# power_dist.net
KiCad netlist of a schematic drawn in EAGLE
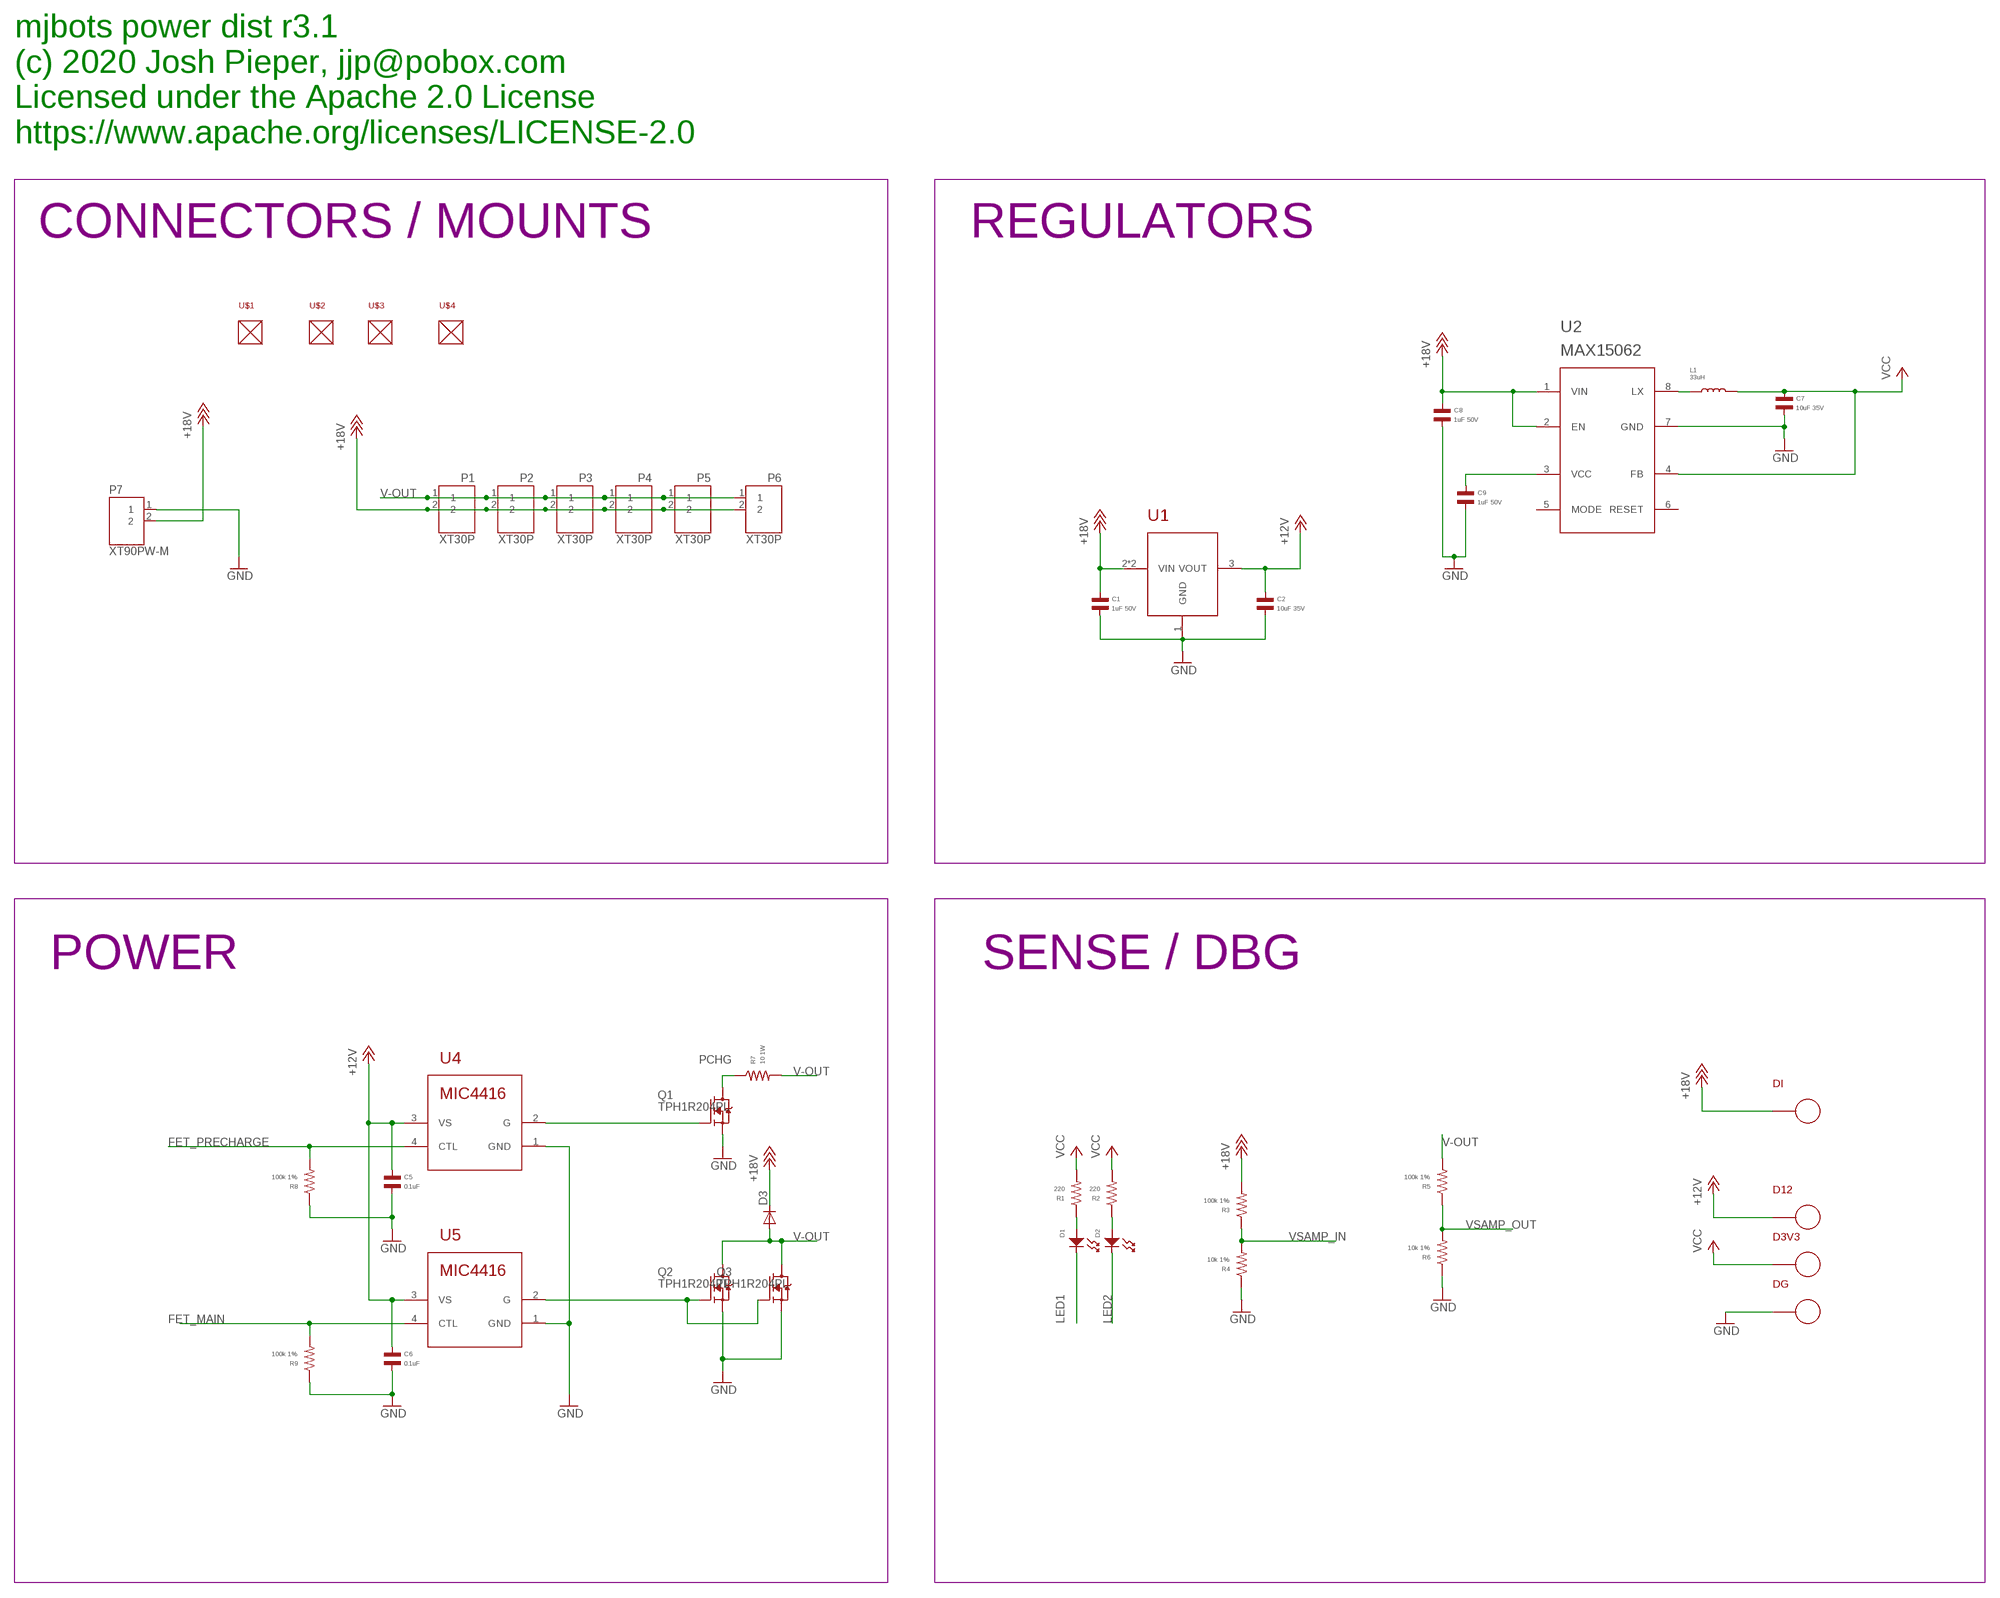
[diagram p0: schematic, sheet 1, part 1 of 2]
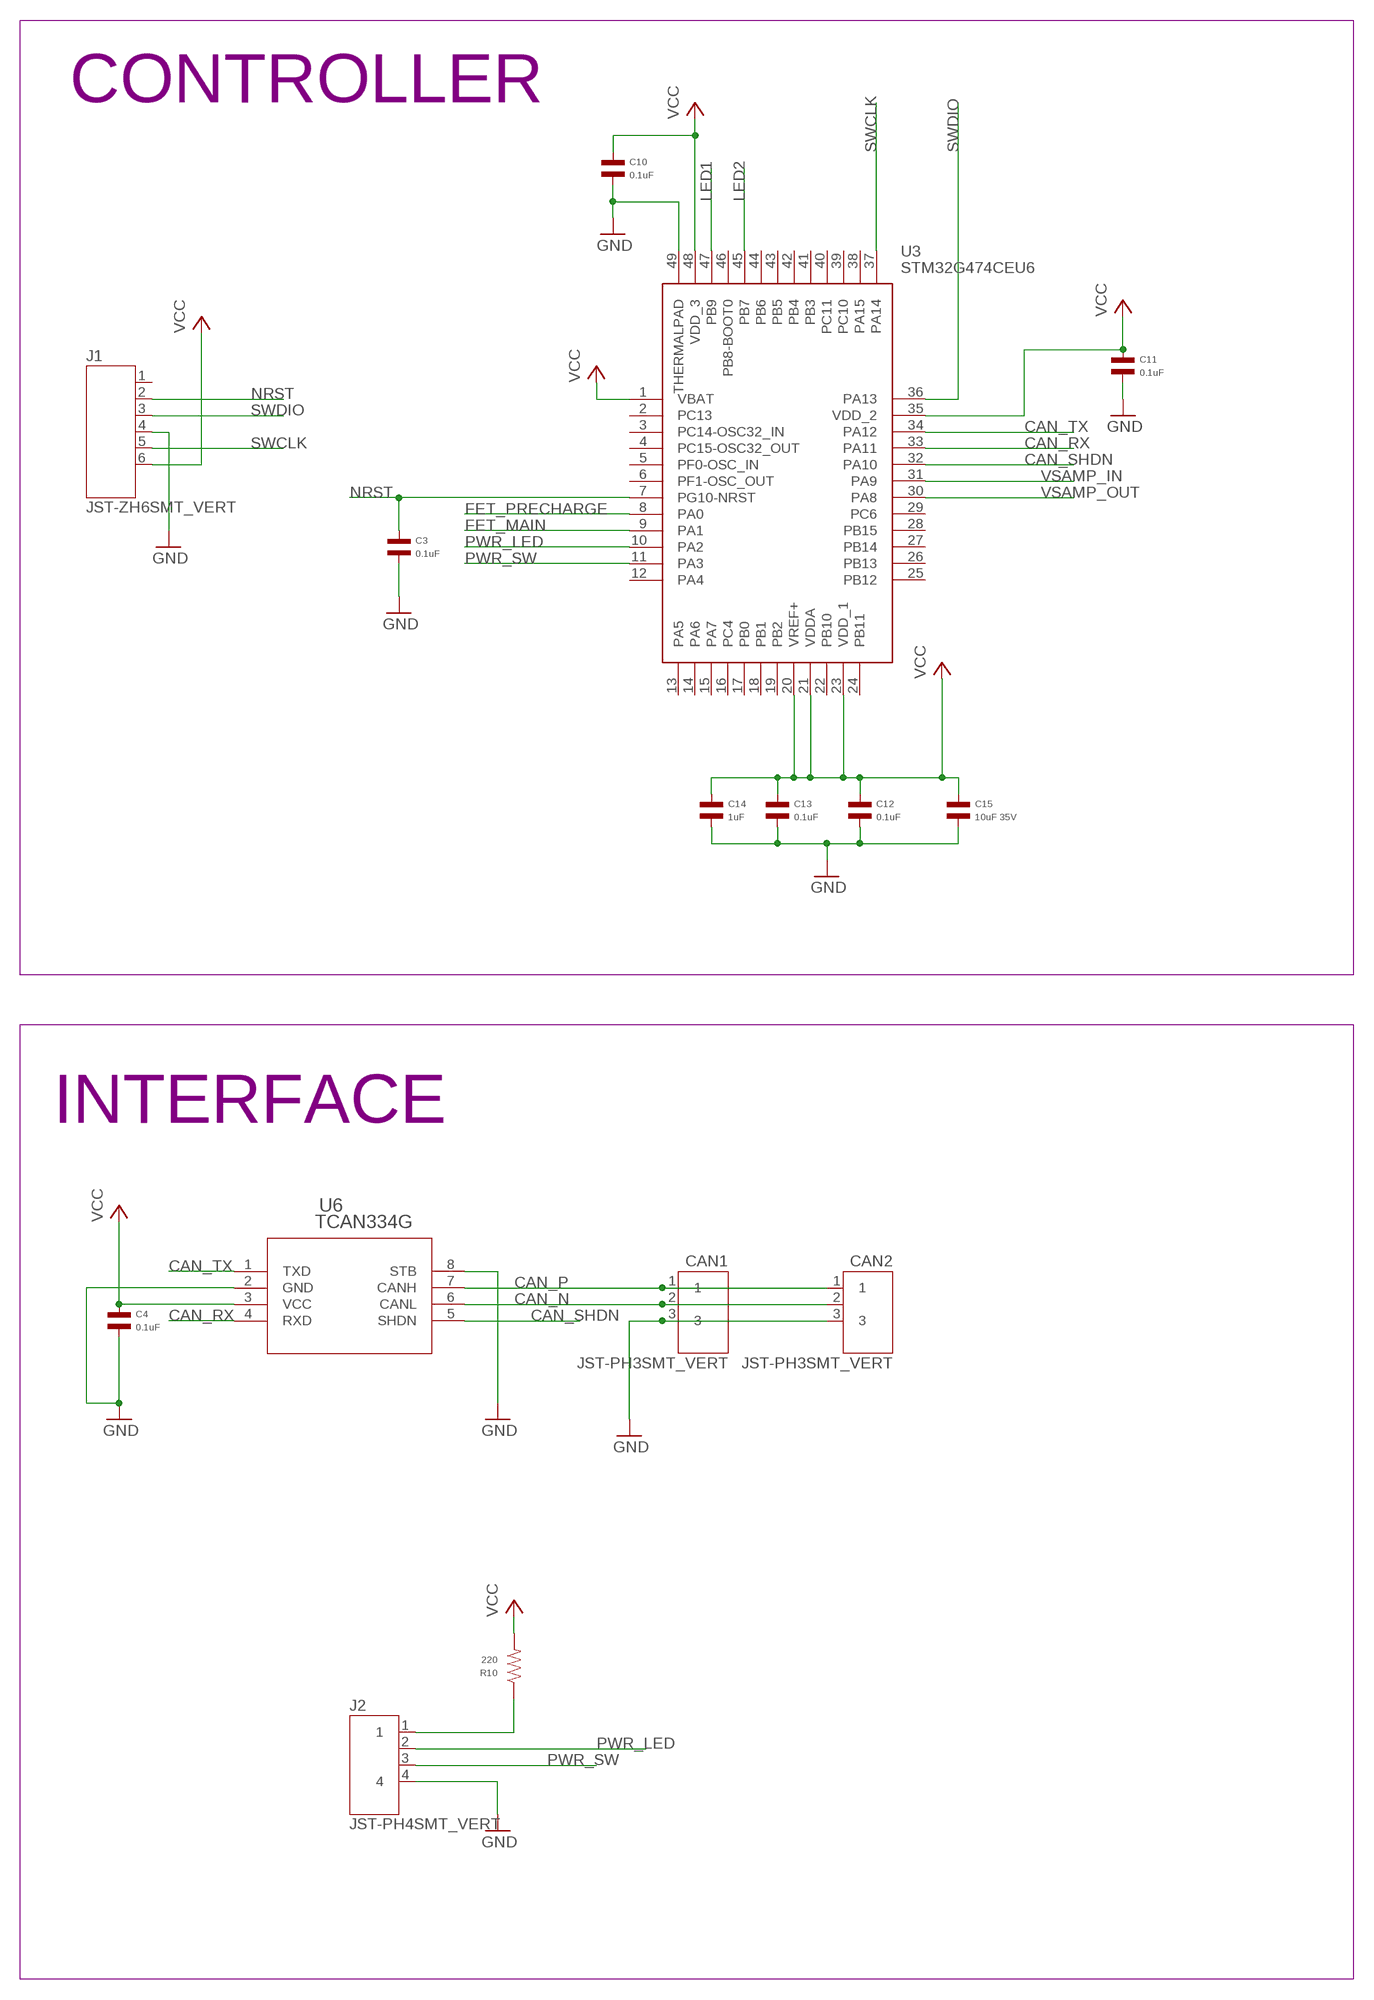
[diagram p1: schematic, sheet 1, part 2 of 2]

(export (version "E")
  (design (tool "Eeschema 10.0.6"))
  (components
    (comp (ref "C1")
      (value "1uF 50V")
      (footprint "eagle-import:C0603")
      (fields (field (name "MF") "SAMSUNG") (field (name "MPN") "CL10A105KB8NNNC"))
      (libsource (lib "eagle-import") (part "CAPACITOR_NP_0603"))
    )
    (comp (ref "C2")
      (value "10uF 35V")
      (footprint "eagle-import:C1206")
      (fields (field (name "MF") "TDK") (field (name "MPN") "CGA5L1X7R1V106K160AC"))
      (libsource (lib "eagle-import") (part "CAPACITOR_NP_1206"))
    )
    (comp (ref "C3")
      (value "0.1uF")
      (footprint "eagle-import:C0402")
      (fields (field (name "HOUSEPART") "1") (field (name "MPN") "MF-CAP-0402-0.1uF"))
      (libsource (lib "eagle-import") (part "CAPACITOR_NP_0402"))
    )
    (comp (ref "C4")
      (value "0.1uF")
      (footprint "eagle-import:C0402")
      (fields (field (name "HOUSEPART") "1") (field (name "MPN") "MF-CAP-0402-0.1uF"))
      (libsource (lib "eagle-import") (part "CAPACITOR_NP_0402"))
    )
    (comp (ref "C5")
      (value "0.1uF")
      (footprint "eagle-import:C0402")
      (fields (field (name "HOUSEPART") "1") (field (name "MPN") "MF-CAP-0402-0.1uF"))
      (libsource (lib "eagle-import") (part "CAPACITOR_NP_0402"))
    )
    (comp (ref "C6")
      (value "0.1uF")
      (footprint "eagle-import:C0402")
      (fields (field (name "HOUSEPART") "1") (field (name "MPN") "MF-CAP-0402-0.1uF"))
      (libsource (lib "eagle-import") (part "CAPACITOR_NP_0402"))
    )
    (comp (ref "C7")
      (value "10uF 35V")
      (footprint "eagle-import:C1206")
      (fields (field (name "MF") "TDK") (field (name "MPN") "CGA5L1X7R1V106K160AC"))
      (libsource (lib "eagle-import") (part "CAPACITOR_NP_1206"))
    )
    (comp (ref "C8")
      (value "1uF 50V")
      (footprint "eagle-import:C0603")
      (fields (field (name "MF") "SAMSUNG") (field (name "MPN") "CL10A105KB8NNNC"))
      (libsource (lib "eagle-import") (part "CAPACITOR_NP_0603"))
    )
    (comp (ref "C9")
      (value "1uF 50V")
      (footprint "eagle-import:C0603")
      (fields (field (name "MF") "SAMSUNG") (field (name "MPN") "CL10A105KB8NNNC"))
      (libsource (lib "eagle-import") (part "CAPACITOR_NP_0603"))
    )
    (comp (ref "C10")
      (value "0.1uF")
      (footprint "eagle-import:C0402")
      (fields (field (name "HOUSEPART") "1") (field (name "MPN") "MF-CAP-0402-0.1uF"))
      (libsource (lib "eagle-import") (part "CAPACITOR_NP_0402"))
    )
    (comp (ref "C11")
      (value "0.1uF")
      (footprint "eagle-import:C0402")
      (fields (field (name "HOUSEPART") "1") (field (name "MPN") "MF-CAP-0402-0.1uF"))
      (libsource (lib "eagle-import") (part "CAPACITOR_NP_0402"))
    )
    (comp (ref "C12")
      (value "0.1uF")
      (footprint "eagle-import:C0402")
      (fields (field (name "HOUSEPART") "1") (field (name "MPN") "MF-CAP-0402-0.1uF"))
      (libsource (lib "eagle-import") (part "CAPACITOR_NP_0402"))
    )
    (comp (ref "C13")
      (value "0.1uF")
      (footprint "eagle-import:C0402")
      (fields (field (name "HOUSEPART") "1") (field (name "MPN") "MF-CAP-0402-0.1uF"))
      (libsource (lib "eagle-import") (part "CAPACITOR_NP_0402"))
    )
    (comp (ref "C14")
      (value "1uF")
      (footprint "eagle-import:C0402")
      (fields (field (name "HOUSEPART") "1") (field (name "MPN") "MF-CAP-0402-1uF"))
      (libsource (lib "eagle-import") (part "CAPACITOR_NP_0402"))
    )
    (comp (ref "C15")
      (value "10uF 35V")
      (footprint "eagle-import:C1206")
      (fields (field (name "MF") "TDK") (field (name "MPN") "CGA5L1X7R1V106K160AC"))
      (libsource (lib "eagle-import") (part "CAPACITOR_NP_1206"))
    )
    (comp (ref "CAN1")
      (value "JST-PH3SMT_VERT")
      (footprint "eagle-import:JST_B3B_PH-SM4-TB(LF)(SN)")
      (fields (field (name "MF") "JST") (field (name "MPN") "B3B-PH-SM4-TB(LF)(SN)"))
      (libsource (lib "eagle-import") (part "JST-PH3SMT_VERT"))
    )
    (comp (ref "CAN2")
      (value "JST-PH3SMT_VERT")
      (footprint "eagle-import:JST_B3B_PH-SM4-TB(LF)(SN)")
      (fields (field (name "MF") "JST") (field (name "MPN") "B3B-PH-SM4-TB(LF)(SN)"))
      (libsource (lib "eagle-import") (part "JST-PH3SMT_VERT"))
    )
    (comp (ref "D1")
      (value "LED_SINGLE-0603")
      (footprint "eagle-import:LED0603")
      (fields
        (field (name "HOUSEPART") "NO")
        (field (name "HOUSEPART_1") "1")
        (field (name "MPN") "MF-LED-0603-RED")
      )
      (libsource (lib "eagle-import") (part "LED_SINGLE-0603"))
    )
    (comp (ref "D2")
      (value "LED_SINGLE-0603")
      (footprint "eagle-import:LED0603")
      (fields
        (field (name "HOUSEPART") "NO")
        (field (name "HOUSEPART_1") "1")
        (field (name "MPN") "MF-LED-0603-RED")
      )
      (libsource (lib "eagle-import") (part "LED_SINGLE-0603"))
    )
    (comp (ref "D3")
      (value "DIODE-")
      (footprint "eagle-import:DO-214AB")
      (fields (field (name "MF") "MICRO COMMERCIAL") (field (name "MPN") "SK510L-TP"))
      (libsource (lib "eagle-import") (part "DIODE-"))
    )
    (comp (ref "D3V3")
      (value "PAD24AWG_PAD")
      (footprint "eagle-import:24AWG_PAD")
      (libsource (lib "eagle-import") (part "PAD24AWG_PAD"))
    )
    (comp (ref "D12")
      (value "PAD24AWG_PAD")
      (footprint "eagle-import:24AWG_PAD")
      (libsource (lib "eagle-import") (part "PAD24AWG_PAD"))
    )
    (comp (ref "DG")
      (value "PAD24AWG_PAD")
      (footprint "eagle-import:24AWG_PAD")
      (libsource (lib "eagle-import") (part "PAD24AWG_PAD"))
    )
    (comp (ref "DI")
      (value "PAD24AWG_PAD")
      (footprint "eagle-import:24AWG_PAD")
      (libsource (lib "eagle-import") (part "PAD24AWG_PAD"))
    )
    (comp (ref "J1")
      (value "JST-ZH6SMT_VERT")
      (footprint "eagle-import:JST_B6B-ZR-SM4-TF(LF)(SN)")
      (fields (field (name "MF") "JST") (field (name "MPN") "B6B-ZR-SM4-TF(LF)(SN)"))
      (libsource (lib "eagle-import") (part "JST-ZH6SMT_VERT"))
    )
    (comp (ref "J2")
      (value "JST-PH4SMT_VERT")
      (footprint "eagle-import:JST_B4B_PH-SM4-TB(LF)(SN)")
      (fields (field (name "MF") "JST") (field (name "MPN") "B4B-PH-SM4-TB(LF)(SN)"))
      (libsource (lib "eagle-import") (part "JST-PH4SMT_VERT"))
    )
    (comp (ref "L1")
      (value "33uH")
      (footprint "eagle-import:L1210")
      (fields (field (name "MF") "TDK") (field (name "MPN") "NLFV32T-330K-EF") (field (name "POPULATE") "1"))
      (libsource (lib "eagle-import") (part "INDUCTOR_1210"))
    )
    (comp (ref "P1")
      (value "XT30P")
      (footprint "eagle-import:XT30P")
      (libsource (lib "eagle-import") (part "XT30P"))
    )
    (comp (ref "P2")
      (value "XT30P")
      (footprint "eagle-import:XT30P")
      (libsource (lib "eagle-import") (part "XT30P"))
    )
    (comp (ref "P3")
      (value "XT30P")
      (footprint "eagle-import:XT30P")
      (libsource (lib "eagle-import") (part "XT30P"))
    )
    (comp (ref "P4")
      (value "XT30P")
      (footprint "eagle-import:XT30P")
      (libsource (lib "eagle-import") (part "XT30P"))
    )
    (comp (ref "P5")
      (value "XT30P")
      (footprint "eagle-import:XT30P")
      (libsource (lib "eagle-import") (part "XT30P"))
    )
    (comp (ref "P6")
      (value "XT30P")
      (footprint "eagle-import:XT30P")
      (libsource (lib "eagle-import") (part "XT30P"))
    )
    (comp (ref "P7")
      (value "XT90PW-M")
      (footprint "eagle-import:XT90PW-M")
      (libsource (lib "eagle-import") (part "XT90PW-M"))
    )
    (comp (ref "Q1")
      (value "TPH1R204PL")
      (footprint "eagle-import:SOP_ADVANCE")
      (fields (field (name "MF") "Toshiba") (field (name "MPN") "TPH1R204PL,L1Q"))
      (libsource (lib "eagle-import") (part "TPH1R204PL"))
    )
    (comp (ref "Q2")
      (value "TPH1R204PL")
      (footprint "eagle-import:SOP_ADVANCE")
      (fields (field (name "MF") "Toshiba") (field (name "MPN") "TPH1R204PL,L1Q"))
      (libsource (lib "eagle-import") (part "TPH1R204PL"))
    )
    (comp (ref "Q3")
      (value "TPH1R204PL")
      (footprint "eagle-import:SOP_ADVANCE")
      (fields (field (name "MF") "Toshiba") (field (name "MPN") "TPH1R204PL,L1Q"))
      (libsource (lib "eagle-import") (part "TPH1R204PL"))
    )
    (comp (ref "R1")
      (value "220")
      (footprint "eagle-import:R0603")
      (fields (field (name "HOUSEPART") "1") (field (name "MPN") "MF-RES-0603-220"))
      (libsource (lib "eagle-import") (part "RESISTOR_0603"))
    )
    (comp (ref "R2")
      (value "220")
      (footprint "eagle-import:R0603")
      (fields (field (name "HOUSEPART") "1") (field (name "MPN") "MF-RES-0603-220"))
      (libsource (lib "eagle-import") (part "RESISTOR_0603"))
    )
    (comp (ref "R3")
      (value "100k 1%")
      (footprint "eagle-import:R0603")
      (fields (field (name "MF") "VISHAY") (field (name "MPN") "CRCW0603100KFKEA"))
      (libsource (lib "eagle-import") (part "RESISTOR_0603"))
    )
    (comp (ref "R4")
      (value "10k 1%")
      (footprint "eagle-import:R0603")
      (fields (field (name "MF") "PANASONIC") (field (name "MPN") "ERJ-3EKF1002V"))
      (libsource (lib "eagle-import") (part "RESISTOR_0603"))
    )
    (comp (ref "R5")
      (value "100k 1%")
      (footprint "eagle-import:R0603")
      (fields (field (name "MF") "VISHAY") (field (name "MPN") "CRCW0603100KFKEA"))
      (libsource (lib "eagle-import") (part "RESISTOR_0603"))
    )
    (comp (ref "R6")
      (value "10k 1%")
      (footprint "eagle-import:R0603")
      (fields (field (name "MF") "PANASONIC") (field (name "MPN") "ERJ-3EKF1002V"))
      (libsource (lib "eagle-import") (part "RESISTOR_0603"))
    )
    (comp (ref "R7")
      (value "10 1W")
      (footprint "eagle-import:R1206")
      (fields (field (name "MF") "Susumu") (field (name "MPN") "HRG3216Q-10R0-D-T1"))
      (libsource (lib "eagle-import") (part "RESISTOR_1206"))
    )
    (comp (ref "R8")
      (value "100k 1%")
      (footprint "eagle-import:R0603")
      (fields (field (name "MF") "VISHAY") (field (name "MPN") "CRCW0603100KFKEA"))
      (libsource (lib "eagle-import") (part "RESISTOR_0603"))
    )
    (comp (ref "R9")
      (value "100k 1%")
      (footprint "eagle-import:R0603")
      (fields (field (name "MF") "VISHAY") (field (name "MPN") "CRCW0603100KFKEA"))
      (libsource (lib "eagle-import") (part "RESISTOR_0603"))
    )
    (comp (ref "R10")
      (value "220")
      (footprint "eagle-import:R0603")
      (fields (field (name "HOUSEPART") "1") (field (name "MPN") "MF-RES-0603-220"))
      (libsource (lib "eagle-import") (part "RESISTOR_0603"))
    )
    (comp (ref "U$1")
      (value "MOUNT")
      (footprint "eagle-import:M2.5MOUNT")
      (libsource (lib "eagle-import") (part "MOUNT"))
    )
    (comp (ref "U$2")
      (value "MOUNT")
      (footprint "eagle-import:M2.5MOUNT")
      (libsource (lib "eagle-import") (part "MOUNT"))
    )
    (comp (ref "U$3")
      (value "MOUNT")
      (footprint "eagle-import:M2.5MOUNT")
      (libsource (lib "eagle-import") (part "MOUNT"))
    )
    (comp (ref "U$4")
      (value "MOUNT")
      (footprint "eagle-import:M2.5MOUNT")
      (libsource (lib "eagle-import") (part "MOUNT"))
    )
    (comp (ref "U1")
      (value "ZXTR2012Z")
      (footprint "eagle-import:SOT89")
      (fields (field (name "MF") "DIODES INC") (field (name "MPN") "ZXTR2012Z-13"))
      (libsource (lib "eagle-import") (part "ZXTR2012Z"))
    )
    (comp (ref "U2")
      (value "MAX150628TDFN")
      (footprint "eagle-import:8TDFN")
      (fields (field (name "MF") "MAXIM") (field (name "MPN") "MAX15062AATA+T"))
      (libsource (lib "eagle-import") (part "MAX150628TDFN"))
    )
    (comp (ref "U3")
      (value "STM32G474CEU6")
      (footprint "eagle-import:QFN50P700X700X60-49N")
      (fields (field (name "MOUSER_PART_NUMBER") "511-STM32G474CEU6") (field (name "MF") "ST"))
      (libsource (lib "eagle-import") (part "STM32G474CEU6"))
    )
    (comp (ref "U4")
      (value "MIC4416")
      (footprint "eagle-import:SOT143")
      (fields (field (name "MF") "MICROCHIP") (field (name "MPN") "MIC4416YM4-TR"))
      (libsource (lib "eagle-import") (part "MIC4416"))
    )
    (comp (ref "U5")
      (value "MIC4416")
      (footprint "eagle-import:SOT143")
      (fields (field (name "MF") "MICROCHIP") (field (name "MPN") "MIC4416YM4-TR"))
      (libsource (lib "eagle-import") (part "MIC4416"))
    )
    (comp (ref "U6")
      (value "TCAN334G")
      (footprint "eagle-import:SOIC8")
      (fields (field (name "MF") "Analog") (field (name "MPN") "LTC2875IS8"))
      (libsource (lib "eagle-import") (part "TCAN334G"))
    )
  )
  (nets
    (net (code "1") (name "+12V") (class "Default")
      (node (ref "C2") (pin "P$1") (pinfunction "P$1_P$1") (pintype "passive"))
      (node (ref "C5") (pin "P$1") (pinfunction "P$1_P$1") (pintype "passive"))
      (node (ref "C6") (pin "P$1") (pinfunction "P$1_P$1") (pintype "passive"))
      (node (ref "D12") (pin "P$1") (pinfunction "P$1_P$1") (pintype "bidirectional"))
      (node (ref "U1") (pin "3") (pinfunction "VOUT_3") (pintype "bidirectional"))
      (node (ref "U4") (pin "3") (pinfunction "VS_3") (pintype "bidirectional"))
      (node (ref "U5") (pin "3") (pinfunction "VS_3") (pintype "bidirectional"))
    )
    (net (code "2") (name "+18V") (class "Default")
      (node (ref "C1") (pin "P$1") (pinfunction "P$1_P$1") (pintype "passive"))
      (node (ref "C8") (pin "P$1") (pinfunction "P$1_P$1") (pintype "passive"))
      (node (ref "D3") (pin "C") (pinfunction "C_C") (pintype "passive"))
      (node (ref "DI") (pin "P$1") (pinfunction "P$1_P$1") (pintype "bidirectional"))
      (node (ref "P1") (pin "2") (pinfunction "2_2") (pintype "passive"))
      (node (ref "P2") (pin "2") (pinfunction "2_2") (pintype "passive"))
      (node (ref "P3") (pin "2") (pinfunction "2_2") (pintype "passive"))
      (node (ref "P4") (pin "2") (pinfunction "2_2") (pintype "passive"))
      (node (ref "P5") (pin "2") (pinfunction "2_2") (pintype "passive"))
      (node (ref "P6") (pin "2") (pinfunction "2_2") (pintype "passive"))
      (node (ref "P7") (pin "2") (pinfunction "2_2") (pintype "passive"))
      (node (ref "R3") (pin "P$2") (pinfunction "P$2_P$2") (pintype "passive"))
      (node (ref "U1") (pin "2") (pinfunction "VIN_2") (pintype "bidirectional"))
      (node (ref "U1") (pin "PAD") (pinfunction "VIN_PAD") (pintype "bidirectional"))
      (node (ref "U2") (pin "1") (pinfunction "VIN_1") (pintype "passive"))
      (node (ref "U2") (pin "2") (pinfunction "EN_2") (pintype "passive"))
    )
    (net (code "3") (name "/CAN_N") (class "Default")
      (node (ref "CAN1") (pin "2") (pinfunction "2_2") (pintype "passive"))
      (node (ref "CAN2") (pin "2") (pinfunction "2_2") (pintype "passive"))
      (node (ref "U6") (pin "6") (pinfunction "CANL_6") (pintype "bidirectional"))
    )
    (net (code "4") (name "/CAN_P") (class "Default")
      (node (ref "CAN1") (pin "1") (pinfunction "1_1") (pintype "passive"))
      (node (ref "CAN2") (pin "1") (pinfunction "1_1") (pintype "passive"))
      (node (ref "U6") (pin "7") (pinfunction "CANH_7") (pintype "bidirectional"))
    )
    (net (code "5") (name "/CAN_RX") (class "Default")
      (node (ref "U3") (pin "33") (pinfunction "PA11_33") (pintype "bidirectional"))
      (node (ref "U6") (pin "4") (pinfunction "RXD_4") (pintype "output"))
    )
    (net (code "6") (name "/CAN_SHDN") (class "Default")
      (node (ref "U3") (pin "32") (pinfunction "PA10_32") (pintype "bidirectional"))
      (node (ref "U6") (pin "5") (pinfunction "SHDN_5") (pintype "input"))
    )
    (net (code "7") (name "/CAN_TX") (class "Default")
      (node (ref "U3") (pin "34") (pinfunction "PA12_34") (pintype "bidirectional"))
      (node (ref "U6") (pin "1") (pinfunction "TXD_1") (pintype "input"))
    )
    (net (code "8") (name "/FET_MAIN") (class "Default")
      (node (ref "R9") (pin "P$2") (pinfunction "P$2_P$2") (pintype "passive"))
      (node (ref "U3") (pin "9") (pinfunction "PA1_9") (pintype "bidirectional"))
      (node (ref "U5") (pin "4") (pinfunction "CTL_4") (pintype "bidirectional"))
    )
    (net (code "9") (name "/FET_PRECHARGE") (class "Default")
      (node (ref "R8") (pin "P$2") (pinfunction "P$2_P$2") (pintype "passive"))
      (node (ref "U3") (pin "8") (pinfunction "PA0_8") (pintype "bidirectional"))
      (node (ref "U4") (pin "4") (pinfunction "CTL_4") (pintype "bidirectional"))
    )
    (net (code "10") (name "/LED1") (class "Default")
      (node (ref "D1") (pin "CATHODE") (pinfunction "CATHODE_CATHODE") (pintype "power_in"))
      (node (ref "U3") (pin "47") (pinfunction "PB9_47") (pintype "bidirectional"))
    )
    (net (code "11") (name "/LED2") (class "Default")
      (node (ref "D2") (pin "CATHODE") (pinfunction "CATHODE_CATHODE") (pintype "power_in"))
      (node (ref "U3") (pin "45") (pinfunction "PB7_45") (pintype "bidirectional"))
    )
    (net (code "12") (name "/NRST") (class "Default")
      (node (ref "C3") (pin "P$1") (pinfunction "P$1_P$1") (pintype "passive"))
      (node (ref "J1") (pin "2") (pinfunction "2_2") (pintype "passive"))
      (node (ref "U3") (pin "7") (pinfunction "PG10-NRST_7") (pintype "bidirectional"))
    )
    (net (code "13") (name "/PCHG") (class "Default")
      (node (ref "Q1") (pin "5") (pinfunction "D_5") (pintype "passive"))
      (node (ref "Q1") (pin "6") (pinfunction "D_6") (pintype "passive"))
      (node (ref "Q1") (pin "7") (pinfunction "D_7") (pintype "passive"))
      (node (ref "Q1") (pin "8") (pinfunction "D_8") (pintype "passive"))
      (node (ref "Q1") (pin "PAD") (pinfunction "D_PAD") (pintype "passive"))
      (node (ref "R7") (pin "P$1") (pinfunction "P$1_P$1") (pintype "passive"))
    )
    (net (code "14") (name "/PWR_LED") (class "Default")
      (node (ref "J2") (pin "2") (pinfunction "2_2") (pintype "passive"))
      (node (ref "U3") (pin "10") (pinfunction "PA2_10") (pintype "bidirectional"))
    )
    (net (code "15") (name "/PWR_SW") (class "Default")
      (node (ref "J2") (pin "3") (pinfunction "3_3") (pintype "passive"))
      (node (ref "U3") (pin "11") (pinfunction "PA3_11") (pintype "bidirectional"))
    )
    (net (code "16") (name "/SWCLK") (class "Default")
      (node (ref "J1") (pin "5") (pinfunction "5_5") (pintype "passive"))
      (node (ref "U3") (pin "37") (pinfunction "PA14_37") (pintype "bidirectional"))
    )
    (net (code "17") (name "/SWDIO") (class "Default")
      (node (ref "J1") (pin "3") (pinfunction "3_3") (pintype "passive"))
      (node (ref "U3") (pin "36") (pinfunction "PA13_36") (pintype "bidirectional"))
    )
    (net (code "18") (name "/V-OUT") (class "Default")
      (node (ref "D3") (pin "A") (pinfunction "A_A") (pintype "passive"))
      (node (ref "P1") (pin "1") (pinfunction "1_1") (pintype "passive"))
      (node (ref "P2") (pin "1") (pinfunction "1_1") (pintype "passive"))
      (node (ref "P3") (pin "1") (pinfunction "1_1") (pintype "passive"))
      (node (ref "P4") (pin "1") (pinfunction "1_1") (pintype "passive"))
      (node (ref "P5") (pin "1") (pinfunction "1_1") (pintype "passive"))
      (node (ref "P6") (pin "1") (pinfunction "1_1") (pintype "passive"))
      (node (ref "Q2") (pin "5") (pinfunction "D_5") (pintype "passive"))
      (node (ref "Q2") (pin "6") (pinfunction "D_6") (pintype "passive"))
      (node (ref "Q2") (pin "7") (pinfunction "D_7") (pintype "passive"))
      (node (ref "Q2") (pin "8") (pinfunction "D_8") (pintype "passive"))
      (node (ref "Q2") (pin "PAD") (pinfunction "D_PAD") (pintype "passive"))
      (node (ref "Q3") (pin "5") (pinfunction "D_5") (pintype "passive"))
      (node (ref "Q3") (pin "6") (pinfunction "D_6") (pintype "passive"))
      (node (ref "Q3") (pin "7") (pinfunction "D_7") (pintype "passive"))
      (node (ref "Q3") (pin "8") (pinfunction "D_8") (pintype "passive"))
      (node (ref "Q3") (pin "PAD") (pinfunction "D_PAD") (pintype "passive"))
      (node (ref "R5") (pin "P$2") (pinfunction "P$2_P$2") (pintype "passive"))
      (node (ref "R7") (pin "P$2") (pinfunction "P$2_P$2") (pintype "passive"))
    )
    (net (code "19") (name "/VSAMP_IN") (class "Default")
      (node (ref "R3") (pin "P$1") (pinfunction "P$1_P$1") (pintype "passive"))
      (node (ref "R4") (pin "P$2") (pinfunction "P$2_P$2") (pintype "passive"))
      (node (ref "U3") (pin "31") (pinfunction "PA9_31") (pintype "bidirectional"))
    )
    (net (code "20") (name "/VSAMP_OUT") (class "Default")
      (node (ref "R5") (pin "P$1") (pinfunction "P$1_P$1") (pintype "passive"))
      (node (ref "R6") (pin "P$2") (pinfunction "P$2_P$2") (pintype "passive"))
      (node (ref "U3") (pin "30") (pinfunction "PA8_30") (pintype "bidirectional"))
    )
    (net (code "21") (name "GND") (class "Default")
      (node (ref "C1") (pin "P$2") (pinfunction "P$2_P$2") (pintype "passive"))
      (node (ref "C10") (pin "P$2") (pinfunction "P$2_P$2") (pintype "passive"))
      (node (ref "C11") (pin "P$2") (pinfunction "P$2_P$2") (pintype "passive"))
      (node (ref "C12") (pin "P$2") (pinfunction "P$2_P$2") (pintype "passive"))
      (node (ref "C13") (pin "P$2") (pinfunction "P$2_P$2") (pintype "passive"))
      (node (ref "C14") (pin "P$2") (pinfunction "P$2_P$2") (pintype "passive"))
      (node (ref "C15") (pin "P$2") (pinfunction "P$2_P$2") (pintype "passive"))
      (node (ref "C2") (pin "P$2") (pinfunction "P$2_P$2") (pintype "passive"))
      (node (ref "C3") (pin "P$2") (pinfunction "P$2_P$2") (pintype "passive"))
      (node (ref "C4") (pin "P$2") (pinfunction "P$2_P$2") (pintype "passive"))
      (node (ref "C5") (pin "P$2") (pinfunction "P$2_P$2") (pintype "passive"))
      (node (ref "C6") (pin "P$2") (pinfunction "P$2_P$2") (pintype "passive"))
      (node (ref "C7") (pin "P$2") (pinfunction "P$2_P$2") (pintype "passive"))
      (node (ref "C8") (pin "P$2") (pinfunction "P$2_P$2") (pintype "passive"))
      (node (ref "C9") (pin "P$2") (pinfunction "P$2_P$2") (pintype "passive"))
      (node (ref "CAN1") (pin "3") (pinfunction "3_3") (pintype "passive"))
      (node (ref "CAN2") (pin "3") (pinfunction "3_3") (pintype "passive"))
      (node (ref "DG") (pin "P$1") (pinfunction "P$1_P$1") (pintype "bidirectional"))
      (node (ref "J1") (pin "4") (pinfunction "4_4") (pintype "passive"))
      (node (ref "J2") (pin "4") (pinfunction "4_4") (pintype "passive"))
      (node (ref "P7") (pin "1") (pinfunction "1_1") (pintype "passive"))
      (node (ref "Q1") (pin "1") (pinfunction "S_1") (pintype "passive"))
      (node (ref "Q1") (pin "2") (pinfunction "S_2") (pintype "passive"))
      (node (ref "Q1") (pin "3") (pinfunction "S_3") (pintype "passive"))
      (node (ref "Q2") (pin "1") (pinfunction "S_1") (pintype "passive"))
      (node (ref "Q2") (pin "2") (pinfunction "S_2") (pintype "passive"))
      (node (ref "Q2") (pin "3") (pinfunction "S_3") (pintype "passive"))
      (node (ref "Q3") (pin "1") (pinfunction "S_1") (pintype "passive"))
      (node (ref "Q3") (pin "2") (pinfunction "S_2") (pintype "passive"))
      (node (ref "Q3") (pin "3") (pinfunction "S_3") (pintype "passive"))
      (node (ref "R4") (pin "P$1") (pinfunction "P$1_P$1") (pintype "passive"))
      (node (ref "R6") (pin "P$1") (pinfunction "P$1_P$1") (pintype "passive"))
      (node (ref "R8") (pin "P$1") (pinfunction "P$1_P$1") (pintype "passive"))
      (node (ref "R9") (pin "P$1") (pinfunction "P$1_P$1") (pintype "passive"))
      (node (ref "U1") (pin "1") (pinfunction "GND_1") (pintype "bidirectional"))
      (node (ref "U2") (pin "7") (pinfunction "GND_7") (pintype "passive"))
      (node (ref "U3") (pin "49") (pinfunction "THERMALPAD_49") (pintype "bidirectional"))
      (node (ref "U4") (pin "1") (pinfunction "GND_1") (pintype "bidirectional"))
      (node (ref "U5") (pin "1") (pinfunction "GND_1") (pintype "bidirectional"))
      (node (ref "U6") (pin "2") (pinfunction "GND_2") (pintype "power_in"))
      (node (ref "U6") (pin "8") (pinfunction "STB_8") (pintype "input"))
    )
    (net (code "22") (name "Net-(D1-PadANODE)") (class "Default")
      (node (ref "D1") (pin "ANODE") (pinfunction "ANODE_ANODE") (pintype "power_in"))
      (node (ref "R1") (pin "P$1") (pinfunction "P$1_P$1") (pintype "passive"))
    )
    (net (code "23") (name "Net-(D2-PadANODE)") (class "Default")
      (node (ref "D2") (pin "ANODE") (pinfunction "ANODE_ANODE") (pintype "power_in"))
      (node (ref "R2") (pin "P$1") (pinfunction "P$1_P$1") (pintype "passive"))
    )
    (net (code "24") (name "Net-(J2-Pad1)") (class "Default")
      (node (ref "J2") (pin "1") (pinfunction "1_1") (pintype "passive"))
      (node (ref "R10") (pin "P$1") (pinfunction "P$1_P$1") (pintype "passive"))
    )
    (net (code "25") (name "Net-(Q1-G)") (class "Default")
      (node (ref "Q1") (pin "4") (pinfunction "G_4") (pintype "passive"))
      (node (ref "U4") (pin "2") (pinfunction "G_2") (pintype "bidirectional"))
    )
    (net (code "26") (name "Net-(Q2-G)") (class "Default")
      (node (ref "Q2") (pin "4") (pinfunction "G_4") (pintype "passive"))
      (node (ref "Q3") (pin "4") (pinfunction "G_4") (pintype "passive"))
      (node (ref "U5") (pin "2") (pinfunction "G_2") (pintype "bidirectional"))
    )
    (net (code "27") (name "Net-(U2-LX)") (class "Default")
      (node (ref "L1") (pin "P$1") (pinfunction "P$1_P$1") (pintype "passive"))
      (node (ref "U2") (pin "8") (pinfunction "LX_8") (pintype "passive"))
    )
    (net (code "28") (name "Net-(U2-VCC)") (class "Default")
      (node (ref "C9") (pin "P$1") (pinfunction "P$1_P$1") (pintype "passive"))
      (node (ref "U2") (pin "3") (pinfunction "VCC_3") (pintype "passive"))
    )
    (net (code "29") (name "VCC") (class "Default")
      (node (ref "C10") (pin "P$1") (pinfunction "P$1_P$1") (pintype "passive"))
      (node (ref "C11") (pin "P$1") (pinfunction "P$1_P$1") (pintype "passive"))
      (node (ref "C12") (pin "P$1") (pinfunction "P$1_P$1") (pintype "passive"))
      (node (ref "C13") (pin "P$1") (pinfunction "P$1_P$1") (pintype "passive"))
      (node (ref "C14") (pin "P$1") (pinfunction "P$1_P$1") (pintype "passive"))
      (node (ref "C15") (pin "P$1") (pinfunction "P$1_P$1") (pintype "passive"))
      (node (ref "C4") (pin "P$1") (pinfunction "P$1_P$1") (pintype "passive"))
      (node (ref "C7") (pin "P$1") (pinfunction "P$1_P$1") (pintype "passive"))
      (node (ref "D3V3") (pin "P$1") (pinfunction "P$1_P$1") (pintype "bidirectional"))
      (node (ref "J1") (pin "6") (pinfunction "6_6") (pintype "passive"))
      (node (ref "L1") (pin "P$2") (pinfunction "P$2_P$2") (pintype "passive"))
      (node (ref "R1") (pin "P$2") (pinfunction "P$2_P$2") (pintype "passive"))
      (node (ref "R10") (pin "P$2") (pinfunction "P$2_P$2") (pintype "passive"))
      (node (ref "R2") (pin "P$2") (pinfunction "P$2_P$2") (pintype "passive"))
      (node (ref "U2") (pin "4") (pinfunction "FB_4") (pintype "passive"))
      (node (ref "U3") (pin "1") (pinfunction "VBAT_1") (pintype "bidirectional"))
      (node (ref "U3") (pin "20") (pinfunction "VREF+_20") (pintype "bidirectional"))
      (node (ref "U3") (pin "21") (pinfunction "VDDA_21") (pintype "bidirectional"))
      (node (ref "U3") (pin "23") (pinfunction "VDD_1_23") (pintype "bidirectional"))
      (node (ref "U3") (pin "35") (pinfunction "VDD_2_35") (pintype "bidirectional"))
      (node (ref "U3") (pin "48") (pinfunction "VDD_3_48") (pintype "bidirectional"))
      (node (ref "U6") (pin "3") (pinfunction "VCC_3") (pintype "power_in"))
    )
    (net (code "30") (name "unconnected-(J1-Pad1)") (class "Default")
      (node (ref "J1") (pin "1") (pinfunction "1_1") (pintype "passive"))
    )
    (net (code "31") (name "unconnected-(U2-MODE-Pad5)") (class "Default")
      (node (ref "U2") (pin "5") (pinfunction "MODE_5") (pintype "passive"))
    )
    (net (code "32") (name "unconnected-(U2-RESET-Pad6)") (class "Default")
      (node (ref "U2") (pin "6") (pinfunction "RESET_6") (pintype "passive"))
    )
    (net (code "33") (name "unconnected-(U3-PA4-Pad12)") (class "Default")
      (node (ref "U3") (pin "12") (pinfunction "PA4_12") (pintype "bidirectional"))
    )
    (net (code "34") (name "unconnected-(U3-PA5-Pad13)") (class "Default")
      (node (ref "U3") (pin "13") (pinfunction "PA5_13") (pintype "bidirectional"))
    )
    (net (code "35") (name "unconnected-(U3-PA6-Pad14)") (class "Default")
      (node (ref "U3") (pin "14") (pinfunction "PA6_14") (pintype "bidirectional"))
    )
    (net (code "36") (name "unconnected-(U3-PA7-Pad15)") (class "Default")
      (node (ref "U3") (pin "15") (pinfunction "PA7_15") (pintype "bidirectional"))
    )
    (net (code "37") (name "unconnected-(U3-PA15-Pad38)") (class "Default")
      (node (ref "U3") (pin "38") (pinfunction "PA15_38") (pintype "bidirectional"))
    )
    (net (code "38") (name "unconnected-(U3-PB0-Pad17)") (class "Default")
      (node (ref "U3") (pin "17") (pinfunction "PB0_17") (pintype "bidirectional"))
    )
    (net (code "39") (name "unconnected-(U3-PB1-Pad18)") (class "Default")
      (node (ref "U3") (pin "18") (pinfunction "PB1_18") (pintype "bidirectional"))
    )
    (net (code "40") (name "unconnected-(U3-PB2-Pad19)") (class "Default")
      (node (ref "U3") (pin "19") (pinfunction "PB2_19") (pintype "bidirectional"))
    )
    (net (code "41") (name "unconnected-(U3-PB3-Pad41)") (class "Default")
      (node (ref "U3") (pin "41") (pinfunction "PB3_41") (pintype "bidirectional"))
    )
    (net (code "42") (name "unconnected-(U3-PB4-Pad42)") (class "Default")
      (node (ref "U3") (pin "42") (pinfunction "PB4_42") (pintype "bidirectional"))
    )
    (net (code "43") (name "unconnected-(U3-PB5-Pad43)") (class "Default")
      (node (ref "U3") (pin "43") (pinfunction "PB5_43") (pintype "bidirectional"))
    )
    (net (code "44") (name "unconnected-(U3-PB6-Pad44)") (class "Default")
      (node (ref "U3") (pin "44") (pinfunction "PB6_44") (pintype "bidirectional"))
    )
    (net (code "45") (name "unconnected-(U3-PB8-BOOT0-Pad46)") (class "Default")
      (node (ref "U3") (pin "46") (pinfunction "PB8-BOOT0_46") (pintype "bidirectional"))
    )
    (net (code "46") (name "unconnected-(U3-PB10-Pad22)") (class "Default")
      (node (ref "U3") (pin "22") (pinfunction "PB10_22") (pintype "bidirectional"))
    )
    (net (code "47") (name "unconnected-(U3-PB11-Pad24)") (class "Default")
      (node (ref "U3") (pin "24") (pinfunction "PB11_24") (pintype "bidirectional"))
    )
    (net (code "48") (name "unconnected-(U3-PB12-Pad25)") (class "Default")
      (node (ref "U3") (pin "25") (pinfunction "PB12_25") (pintype "bidirectional"))
    )
    (net (code "49") (name "unconnected-(U3-PB13-Pad26)") (class "Default")
      (node (ref "U3") (pin "26") (pinfunction "PB13_26") (pintype "bidirectional"))
    )
    (net (code "50") (name "unconnected-(U3-PB14-Pad27)") (class "Default")
      (node (ref "U3") (pin "27") (pinfunction "PB14_27") (pintype "bidirectional"))
    )
    (net (code "51") (name "unconnected-(U3-PB15-Pad28)") (class "Default")
      (node (ref "U3") (pin "28") (pinfunction "PB15_28") (pintype "bidirectional"))
    )
    (net (code "52") (name "unconnected-(U3-PC4-Pad16)") (class "Default")
      (node (ref "U3") (pin "16") (pinfunction "PC4_16") (pintype "bidirectional"))
    )
    (net (code "53") (name "unconnected-(U3-PC6-Pad29)") (class "Default")
      (node (ref "U3") (pin "29") (pinfunction "PC6_29") (pintype "bidirectional"))
    )
    (net (code "54") (name "unconnected-(U3-PC10-Pad39)") (class "Default")
      (node (ref "U3") (pin "39") (pinfunction "PC10_39") (pintype "bidirectional"))
    )
    (net (code "55") (name "unconnected-(U3-PC11-Pad40)") (class "Default")
      (node (ref "U3") (pin "40") (pinfunction "PC11_40") (pintype "bidirectional"))
    )
    (net (code "56") (name "unconnected-(U3-PC13-Pad2)") (class "Default")
      (node (ref "U3") (pin "2") (pinfunction "PC13_2") (pintype "bidirectional"))
    )
    (net (code "57") (name "unconnected-(U3-PC14-OSC32_IN-Pad3)") (class "Default")
      (node (ref "U3") (pin "3") (pinfunction "PC14-OSC32_IN_3") (pintype "bidirectional"))
    )
    (net (code "58") (name "unconnected-(U3-PC15-OSC32_OUT-Pad4)") (class "Default")
      (node (ref "U3") (pin "4") (pinfunction "PC15-OSC32_OUT_4") (pintype "bidirectional"))
    )
    (net (code "59") (name "unconnected-(U3-PF0-OSC_IN-Pad5)") (class "Default")
      (node (ref "U3") (pin "5") (pinfunction "PF0-OSC_IN_5") (pintype "bidirectional"))
    )
    (net (code "60") (name "unconnected-(U3-PF1-OSC_OUT-Pad6)") (class "Default")
      (node (ref "U3") (pin "6") (pinfunction "PF1-OSC_OUT_6") (pintype "bidirectional"))
    )
  )
)
